# lm1875_amplifier.net
KiCad netlist of a schematic drawn in Altium Designer
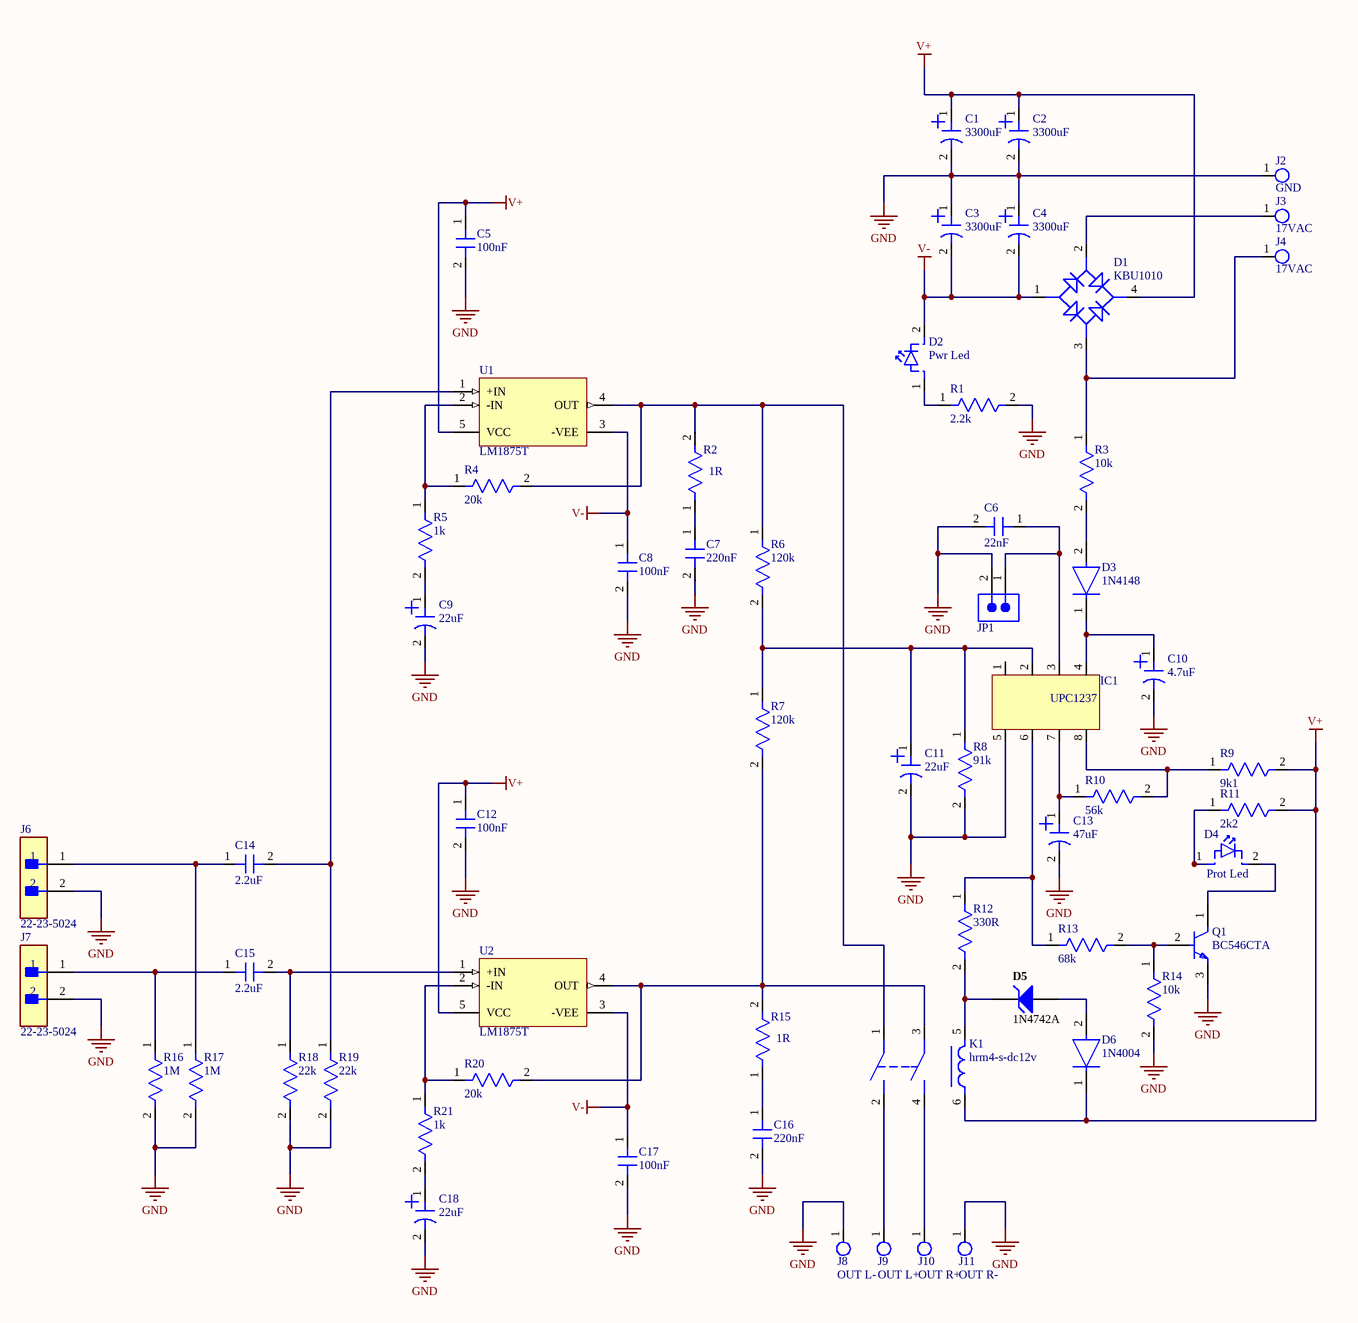
[diagram p0: lm1875 amplifier.SchDoc]

(export (version "E")
  (design (tool "Eeschema 10.0.6"))
  (components
    (comp (ref "C1")
      (value "3300uF")
      (footprint "Capacitor electrolytic 16x21mm")
      (libsource (lib "lm1875") (part "Capacitor 16x21mm"))
    )
    (comp (ref "C2")
      (value "3300uF")
      (footprint "Capacitor electrolytic 16x21mm")
      (libsource (lib "lm1875") (part "Capacitor 16x21mm"))
    )
    (comp (ref "C3")
      (value "3300uF")
      (footprint "Capacitor electrolytic 16x21mm")
      (libsource (lib "lm1875") (part "Capacitor 16x21mm"))
    )
    (comp (ref "C4")
      (value "3300uF")
      (footprint "Capacitor electrolytic 16x21mm")
      (libsource (lib "lm1875") (part "Capacitor 16x21mm"))
    )
    (comp (ref "C5")
      (value "100nF")
      (footprint "Capacitor 3x7mm")
      (libsource (lib "Schlib1") (part "Capacitor 3x7mm"))
    )
    (comp (ref "C6")
      (value "22nF")
      (footprint "Capacitor 2.5x5mm")
      (libsource (lib "Schlib1") (part "Capacitor 2.5x5mm"))
    )
    (comp (ref "C7")
      (value "220nF")
      (footprint "Capacitor MKT 5x13mm")
      (libsource (lib "Schlib1") (part "Capacitor MKT 5x13mm"))
    )
    (comp (ref "C8")
      (value "100nF")
      (footprint "Capacitor 3x7mm")
      (libsource (lib "Schlib1") (part "Capacitor 3x7mm"))
    )
    (comp (ref "C9")
      (value "22uF")
      (footprint "Capacitor 5x11mm")
      (libsource (lib "Schlib1") (part "Capacitor 5x11mm"))
    )
    (comp (ref "C10")
      (value "4.7uF")
      (footprint "Capacitor 5x11mm")
      (libsource (lib "Schlib1") (part "Capacitor 5x11mm"))
    )
    (comp (ref "C11")
      (value "22uF")
      (footprint "Capacitor 5x11mm")
      (libsource (lib "Schlib1") (part "Capacitor 5x11mm"))
    )
    (comp (ref "C12")
      (value "100nF")
      (footprint "Capacitor 3x7mm")
      (libsource (lib "Schlib1") (part "Capacitor 3x7mm"))
    )
    (comp (ref "C13")
      (value "47uF")
      (footprint "Capacitor 6x11mm")
      (libsource (lib "Schlib1") (part "Capacitor 6x11mm"))
    )
    (comp (ref "C14")
      (value "2.2uF")
      (footprint "Capacitor Bipolar 10x16mm Axial")
      (libsource (lib "Schlib1") (part "Capacitor Bipolar 10x16mm Axial"))
    )
    (comp (ref "C15")
      (value "2.2uF")
      (footprint "Capacitor Bipolar 10x16mm Axial")
      (libsource (lib "Schlib1") (part "Capacitor Bipolar 10x16mm Axial"))
    )
    (comp (ref "C16")
      (value "220nF")
      (footprint "Capacitor MKT 5x13mm")
      (libsource (lib "Schlib1") (part "Capacitor MKT 5x13mm"))
    )
    (comp (ref "C17")
      (value "100nF")
      (footprint "Capacitor 3x7mm")
      (libsource (lib "Schlib1") (part "Capacitor 3x7mm"))
    )
    (comp (ref "C18")
      (value "22uF")
      (footprint "Capacitor 5x11mm")
      (libsource (lib "Schlib1") (part "Capacitor 5x11mm"))
    )
    (comp (ref "D1")
      (value "KBU1010")
      (footprint "KBU Rectifier")
      (libsource (lib "Schlib1") (part "Diode Rectifier KBU"))
    )
    (comp (ref "D2") (value "Pwr Led") (footprint "led 3mm") (libsource (lib "Schlib1") (part "Led 3mm")))
    (comp (ref "D3")
      (value "1N4148")
      (footprint "FP-017AG-MFG")
      (description "DIODE GEN PURP 100V 200MA DO35")
      (fields (field (name "VOLTAGE") "100V"))
      (libsource (lib "Altium Content Vault") (part "d7152d700b627762746794eb795d46e"))
    )
    (comp (ref "D4") (value "Prot Led") (footprint "led 3mm") (libsource (lib "Schlib1") (part "Led 3mm")))
    (comp (ref "D5")
      (value "1N4742A")
      (footprint "FAIR-DO-41-2_V")
      (description "Zener Diode, 12V, 1W, 5%, -65 to 200 degC, 2-Pin DO-41, Body 2.72 x 5.2 mm, RoHS")
      (fields (field (name "TOLERANCE") "5%") (field (name "MANUFACTURER") "Fairchild Semiconductor"))
      (libsource (lib "Altium Content Vault") (part "FAIR-DZEN-A1K2-2"))
    )
    (comp (ref "D6")
      (value "1N4004")
      (footprint "FP-DO-41-MFG")
      (description "DIODE GEN PURP 400V 1A DO41")
      (libsource (lib "Altium Content Vault") (part "d7152d700b627762746794eb795d46e"))
    )
    (comp (ref "IC1") (value "UPC1237") (footprint "SIP 8 PIN") (libsource (lib "Schlib1") (part "UPC1237")))
    (comp (ref "J2")
      (value "GND")
      (footprint "Terminal 6.3mm male")
      (libsource (lib "Schlib1") (part "6.3mm Male Terminal"))
    )
    (comp (ref "J3")
      (value "17VAC")
      (footprint "Terminal 6.3mm male")
      (libsource (lib "Schlib1") (part "6.3mm Male Terminal"))
    )
    (comp (ref "J4")
      (value "17VAC")
      (footprint "Terminal 6.3mm male")
      (libsource (lib "Schlib1") (part "6.3mm Male Terminal"))
    )
    (comp (ref "J6")
      (value "22-23-5024")
      (footprint "FP-22-23-5024-MFG")
      (description "CONN HEADER VERT 2POS 2.54MM")
      (fields
        (field (name "MANUFACTURER") "Molex")
        (field (name "OCTOPART") "https://octopart.com/22-23-5024-molex-6792956")
      )
      (libsource (lib "Altium Content Vault") (part "3bc925449376181038e59eaffc5286c"))
    )
    (comp (ref "J7")
      (value "22-23-5024")
      (footprint "FP-22-23-5024-MFG")
      (description "CONN HEADER VERT 2POS 2.54MM")
      (fields
        (field (name "MANUFACTURER") "Molex")
        (field (name "OCTOPART") "https://octopart.com/22-23-5024-molex-6792956")
      )
      (libsource (lib "Altium Content Vault") (part "3bc925449376181038e59eaffc5286c"))
    )
    (comp (ref "J8")
      (value "OUT L-")
      (footprint "Terminal 6.3mm male")
      (libsource (lib "Schlib1") (part "6.3mm Male Terminal"))
    )
    (comp (ref "J9")
      (value "OUT L+")
      (footprint "Terminal 6.3mm male")
      (libsource (lib "Schlib1") (part "6.3mm Male Terminal"))
    )
    (comp (ref "J10")
      (value "OUT R+")
      (footprint "Terminal 6.3mm male")
      (libsource (lib "Schlib1") (part "6.3mm Male Terminal"))
    )
    (comp (ref "J11")
      (value "OUT R-")
      (footprint "Terminal 6.3mm male")
      (libsource (lib "Schlib1") (part "6.3mm Male Terminal"))
    )
    (comp (ref "JP1")
      (value "~")
      (footprint "61300211121")
      (libsource (lib "Altium Content Vault") (part "Header_Male_1R_02P"))
    )
    (comp (ref "K1")
      (value "hrm4-s-dc12v")
      (footprint "Relay hrm4-s-dc12v")
      (libsource (lib "Schlib1") (part "Relay hrm4-s-dc12v"))
    )
    (comp (ref "Q1")
      (value "BC546CTA")
      (footprint "FP-135AR-MFG")
      (description "BC546CTA Small Signal Bipolar Transistor, 0.1A I(C), 65V V(BR)CEO, 1-Element, NPN, Silicon, TO-92")
      (libsource (lib "Altium Content Vault") (part "ddb5dc480c9317d3b8a15cf6cf16fd3"))
    )
    (comp (ref "R1")
      (value "2.2k")
      (footprint "Resistor 0207 1/4W")
      (libsource (lib "lm1875") (part "Resistor"))
    )
    (comp (ref "R2") (value "1R") (footprint "Resistor 1W") (libsource (lib "Schlib1") (part "Resistor 1W")))
    (comp (ref "R3")
      (value "10k")
      (footprint "Resistor 0207 1/4W")
      (libsource (lib "lm1875") (part "Resistor"))
    )
    (comp (ref "R4")
      (value "20k")
      (footprint "Resistor 0207 1/4W wide legs")
      (libsource (lib "lm1875") (part "Resistor"))
    )
    (comp (ref "R5")
      (value "1k")
      (footprint "Resistor 0207 1/4W")
      (libsource (lib "lm1875") (part "Resistor"))
    )
    (comp (ref "R6")
      (value "120k")
      (footprint "Resistor 0207 1/4W")
      (libsource (lib "lm1875") (part "Resistor"))
    )
    (comp (ref "R7")
      (value "120k")
      (footprint "Resistor 0207 1/4W")
      (libsource (lib "lm1875") (part "Resistor"))
    )
    (comp (ref "R8")
      (value "91k")
      (footprint "Resistor 0207 1/4W")
      (libsource (lib "lm1875") (part "Resistor"))
    )
    (comp (ref "R9")
      (value "9k1")
      (footprint "Resistor 0207 1/4W")
      (libsource (lib "lm1875") (part "Resistor"))
    )
    (comp (ref "R10")
      (value "56k")
      (footprint "Resistor 0207 1/4W")
      (libsource (lib "lm1875") (part "Resistor"))
    )
    (comp (ref "R11")
      (value "2k2")
      (footprint "Resistor 0207 1/4W")
      (libsource (lib "lm1875") (part "Resistor"))
    )
    (comp (ref "R12")
      (value "330R")
      (footprint "Resistor 0207 1/4W")
      (libsource (lib "lm1875") (part "Resistor"))
    )
    (comp (ref "R13")
      (value "68k")
      (footprint "Resistor 0207 1/4W")
      (libsource (lib "lm1875") (part "Resistor"))
    )
    (comp (ref "R14")
      (value "10k")
      (footprint "Resistor 0207 1/4W")
      (libsource (lib "lm1875") (part "Resistor"))
    )
    (comp (ref "R15") (value "1R") (footprint "Resistor 1W") (libsource (lib "Schlib1") (part "Resistor 1W")))
    (comp (ref "R16")
      (value "1M")
      (footprint "Resistor 0207 1/4W")
      (libsource (lib "lm1875") (part "Resistor"))
    )
    (comp (ref "R17")
      (value "1M")
      (footprint "Resistor 0207 1/4W")
      (libsource (lib "lm1875") (part "Resistor"))
    )
    (comp (ref "R18")
      (value "22k")
      (footprint "Resistor 0207 1/4W")
      (libsource (lib "lm1875") (part "Resistor"))
    )
    (comp (ref "R19")
      (value "22k")
      (footprint "Resistor 0207 1/4W")
      (libsource (lib "lm1875") (part "Resistor"))
    )
    (comp (ref "R20")
      (value "20k")
      (footprint "Resistor 0207 1/4W wide legs")
      (libsource (lib "lm1875") (part "Resistor"))
    )
    (comp (ref "R21")
      (value "1k")
      (footprint "Resistor 0207 1/4W")
      (libsource (lib "lm1875") (part "Resistor"))
    )
    (comp (ref "U1")
      (value "LM1875T")
      (footprint "NDH0005A")
      (description "20-W Audio Power Amplifier, 5-pin TO-220")
      (fields (field (name "MANUFACTURER") "Texas Instruments"))
      (libsource (lib "Altium Content Vault") (part "AMP-APA-LM1875-5"))
    )
    (comp (ref "U2")
      (value "LM1875T")
      (footprint "NDH0005A")
      (description "20-W Audio Power Amplifier, 5-pin TO-220")
      (fields (field (name "MANUFACTURER") "Texas Instruments"))
      (libsource (lib "Altium Content Vault") (part "AMP-APA-LM1875-5"))
    )
  )
  (nets
    (net (code "1") (name "GND") (class "Default")
      (node (ref "C1") (pin "2") (pintype "passive"))
      (node (ref "C10") (pin "2") (pintype "passive"))
      (node (ref "C11") (pin "2") (pintype "passive"))
      (node (ref "C12") (pin "2") (pintype "passive"))
      (node (ref "C13") (pin "2") (pintype "passive"))
      (node (ref "C16") (pin "2") (pintype "passive"))
      (node (ref "C17") (pin "2") (pintype "passive"))
      (node (ref "C18") (pin "2") (pintype "passive"))
      (node (ref "C2") (pin "2") (pintype "passive"))
      (node (ref "C3") (pin "1") (pintype "passive"))
      (node (ref "C4") (pin "1") (pintype "passive"))
      (node (ref "C5") (pin "2") (pintype "passive"))
      (node (ref "C6") (pin "2") (pintype "passive"))
      (node (ref "C7") (pin "2") (pintype "passive"))
      (node (ref "C8") (pin "2") (pintype "passive"))
      (node (ref "C9") (pin "2") (pintype "passive"))
      (node (ref "IC1") (pin "5") (pintype "passive"))
      (node (ref "J11") (pin "1") (pintype "passive"))
      (node (ref "J2") (pin "1") (pintype "passive"))
      (node (ref "J6") (pin "2") (pinfunction "2_2") (pintype "passive"))
      (node (ref "J7") (pin "2") (pinfunction "2_2") (pintype "passive"))
      (node (ref "J8") (pin "1") (pintype "passive"))
      (node (ref "JP1") (pin "2") (pinfunction "2_2") (pintype "passive"))
      (node (ref "Q1") (pin "3") (pinfunction "E_3") (pintype "passive"))
      (node (ref "R1") (pin "2") (pintype "passive"))
      (node (ref "R14") (pin "2") (pintype "passive"))
      (node (ref "R16") (pin "2") (pintype "passive"))
      (node (ref "R17") (pin "2") (pintype "passive"))
      (node (ref "R18") (pin "2") (pintype "passive"))
      (node (ref "R19") (pin "2") (pintype "passive"))
      (node (ref "R8") (pin "2") (pintype "passive"))
    )
    (net (code "2") (name "Net-(C6-Pad1)") (class "Default")
      (node (ref "C6") (pin "1") (pintype "passive"))
      (node (ref "IC1") (pin "3") (pintype "passive"))
      (node (ref "JP1") (pin "1") (pinfunction "1_1") (pintype "passive"))
    )
    (net (code "3") (name "Net-(C7-Pad1)") (class "Default")
      (node (ref "C7") (pin "1") (pintype "passive"))
      (node (ref "R2") (pin "1") (pintype "passive"))
    )
    (net (code "4") (name "Net-(C9-Pad1)") (class "Default")
      (node (ref "C9") (pin "1") (pintype "passive"))
      (node (ref "R5") (pin "2") (pintype "passive"))
    )
    (net (code "5") (name "Net-(C11-Pad1)") (class "Default")
      (node (ref "C11") (pin "1") (pintype "passive"))
      (node (ref "IC1") (pin "2") (pintype "passive"))
      (node (ref "R6") (pin "2") (pintype "passive"))
      (node (ref "R7") (pin "1") (pintype "passive"))
      (node (ref "R8") (pin "1") (pintype "passive"))
    )
    (net (code "6") (name "Net-(C13-Pad1)") (class "Default")
      (node (ref "C13") (pin "1") (pintype "passive"))
      (node (ref "IC1") (pin "7") (pintype "passive"))
      (node (ref "R10") (pin "1") (pintype "passive"))
    )
    (net (code "7") (name "Net-(C14-Pad1)") (class "Default")
      (node (ref "C14") (pin "1") (pintype "passive"))
      (node (ref "J6") (pin "1") (pinfunction "1_1") (pintype "passive"))
      (node (ref "R17") (pin "1") (pintype "passive"))
    )
    (net (code "8") (name "Net-(C15-Pad1)") (class "Default")
      (node (ref "C15") (pin "1") (pintype "passive"))
      (node (ref "J7") (pin "1") (pinfunction "1_1") (pintype "passive"))
      (node (ref "R16") (pin "1") (pintype "passive"))
    )
    (net (code "9") (name "Net-(C16-Pad1)") (class "Default")
      (node (ref "C16") (pin "1") (pintype "passive"))
      (node (ref "R15") (pin "1") (pintype "passive"))
    )
    (net (code "10") (name "Net-(C18-Pad1)") (class "Default")
      (node (ref "C18") (pin "1") (pintype "passive"))
      (node (ref "R21") (pin "2") (pintype "passive"))
    )
    (net (code "11") (name "Net-(D1-Pad2)") (class "Default")
      (node (ref "D1") (pin "2") (pintype "passive"))
      (node (ref "J3") (pin "1") (pintype "passive"))
    )
    (net (code "12") (name "Net-(D1-Pad3)") (class "Default")
      (node (ref "D1") (pin "3") (pintype "passive"))
      (node (ref "J4") (pin "1") (pintype "passive"))
      (node (ref "R3") (pin "1") (pintype "passive"))
    )
    (net (code "13") (name "Net-(D2-Pad1)") (class "Default")
      (node (ref "D2") (pin "1") (pintype "passive"))
      (node (ref "R1") (pin "1") (pintype "passive"))
    )
    (net (code "14") (name "Net-(D3-A)") (class "Default")
      (node (ref "D3") (pin "2") (pinfunction "A_2") (pintype "passive"))
      (node (ref "R3") (pin "2") (pintype "passive"))
    )
    (net (code "15") (name "Net-(D3-C)") (class "Default")
      (node (ref "C10") (pin "1") (pintype "passive"))
      (node (ref "D3") (pin "1") (pinfunction "C_1") (pintype "passive"))
      (node (ref "IC1") (pin "4") (pintype "passive"))
    )
    (net (code "16") (name "Net-(D4-Pad1)") (class "Default")
      (node (ref "D4") (pin "1") (pintype "passive"))
      (node (ref "R11") (pin "1") (pintype "passive"))
    )
    (net (code "17") (name "Net-(D5-A)") (class "Default")
      (node (ref "D5") (pin "1") (pinfunction "A_1") (pintype "passive"))
      (node (ref "D6") (pin "2") (pinfunction "A_2") (pintype "passive"))
    )
    (net (code "18") (name "Net-(D5-K)") (class "Default")
      (node (ref "D5") (pin "2") (pinfunction "K_2") (pintype "passive"))
      (node (ref "K1") (pin "5") (pintype "passive"))
      (node (ref "R12") (pin "2") (pintype "passive"))
    )
    (net (code "19") (name "Net-(IC1-Pad6)") (class "Default")
      (node (ref "IC1") (pin "6") (pintype "passive"))
      (node (ref "R12") (pin "1") (pintype "passive"))
      (node (ref "R13") (pin "1") (pintype "passive"))
    )
    (net (code "20") (name "Net-(IC1-Pad8)") (class "Default")
      (node (ref "IC1") (pin "8") (pintype "passive"))
      (node (ref "R10") (pin "2") (pintype "passive"))
      (node (ref "R9") (pin "1") (pintype "passive"))
    )
    (net (code "21") (name "Net-(J9-Pad1)") (class "Default")
      (node (ref "J9") (pin "1") (pintype "passive"))
      (node (ref "K1") (pin "2") (pintype "passive"))
    )
    (net (code "22") (name "Net-(J10-Pad1)") (class "Default")
      (node (ref "J10") (pin "1") (pintype "passive"))
      (node (ref "K1") (pin "4") (pintype "passive"))
    )
    (net (code "23") (name "Net-(Q1-B)") (class "Default")
      (node (ref "Q1") (pin "2") (pinfunction "B_2") (pintype "passive"))
      (node (ref "R13") (pin "2") (pintype "passive"))
      (node (ref "R14") (pin "1") (pintype "passive"))
    )
    (net (code "24") (name "Net-(Q1-C)") (class "Default")
      (node (ref "D4") (pin "2") (pintype "passive"))
      (node (ref "Q1") (pin "1") (pinfunction "C_1") (pintype "passive"))
    )
    (net (code "25") (name "Net-(U1-+IN)") (class "Default")
      (node (ref "C14") (pin "2") (pintype "passive"))
      (node (ref "R19") (pin "1") (pintype "passive"))
      (node (ref "U1") (pin "1") (pinfunction "+IN_1") (pintype "input"))
    )
    (net (code "26") (name "Net-(U1--IN)") (class "Default")
      (node (ref "R4") (pin "1") (pintype "passive"))
      (node (ref "R5") (pin "1") (pintype "passive"))
      (node (ref "U1") (pin "2") (pinfunction "-IN_2") (pintype "input"))
    )
    (net (code "27") (name "Net-(U1-OUT)") (class "Default")
      (node (ref "K1") (pin "1") (pintype "passive"))
      (node (ref "R2") (pin "2") (pintype "passive"))
      (node (ref "R4") (pin "2") (pintype "passive"))
      (node (ref "R6") (pin "1") (pintype "passive"))
      (node (ref "U1") (pin "4") (pinfunction "OUT_4") (pintype "output"))
    )
    (net (code "28") (name "Net-(U2-+IN)") (class "Default")
      (node (ref "C15") (pin "2") (pintype "passive"))
      (node (ref "R18") (pin "1") (pintype "passive"))
      (node (ref "U2") (pin "1") (pinfunction "+IN_1") (pintype "input"))
    )
    (net (code "29") (name "Net-(U2--IN)") (class "Default")
      (node (ref "R20") (pin "1") (pintype "passive"))
      (node (ref "R21") (pin "1") (pintype "passive"))
      (node (ref "U2") (pin "2") (pinfunction "-IN_2") (pintype "input"))
    )
    (net (code "30") (name "Net-(U2-OUT)") (class "Default")
      (node (ref "K1") (pin "3") (pintype "passive"))
      (node (ref "R15") (pin "2") (pintype "passive"))
      (node (ref "R20") (pin "2") (pintype "passive"))
      (node (ref "R7") (pin "2") (pintype "passive"))
      (node (ref "U2") (pin "4") (pinfunction "OUT_4") (pintype "output"))
    )
    (net (code "31") (name "V+") (class "Default")
      (node (ref "C1") (pin "1") (pintype "passive"))
      (node (ref "C12") (pin "1") (pintype "passive"))
      (node (ref "C2") (pin "1") (pintype "passive"))
      (node (ref "C5") (pin "1") (pintype "passive"))
      (node (ref "D1") (pin "4") (pintype "passive"))
      (node (ref "D6") (pin "1") (pinfunction "C_1") (pintype "passive"))
      (node (ref "K1") (pin "6") (pintype "passive"))
      (node (ref "R11") (pin "2") (pintype "passive"))
      (node (ref "R9") (pin "2") (pintype "passive"))
      (node (ref "U1") (pin "5") (pinfunction "VCC_5") (pintype "power_in"))
      (node (ref "U2") (pin "5") (pinfunction "VCC_5") (pintype "power_in"))
    )
    (net (code "32") (name "V-") (class "Default")
      (node (ref "C17") (pin "1") (pintype "passive"))
      (node (ref "C3") (pin "2") (pintype "passive"))
      (node (ref "C4") (pin "2") (pintype "passive"))
      (node (ref "C8") (pin "1") (pintype "passive"))
      (node (ref "D1") (pin "1") (pintype "passive"))
      (node (ref "D2") (pin "2") (pintype "passive"))
      (node (ref "U1") (pin "3") (pinfunction "-VEE_3") (pintype "power_in"))
      (node (ref "U2") (pin "3") (pinfunction "-VEE_3") (pintype "power_in"))
    )
    (net (code "33") (name "unconnected-(IC1-Pad1)") (class "Default")
      (node (ref "IC1") (pin "1") (pintype "passive"))
    )
  )
)
